# Sheet1.net
KiCad netlist of a schematic drawn in Altium Designer
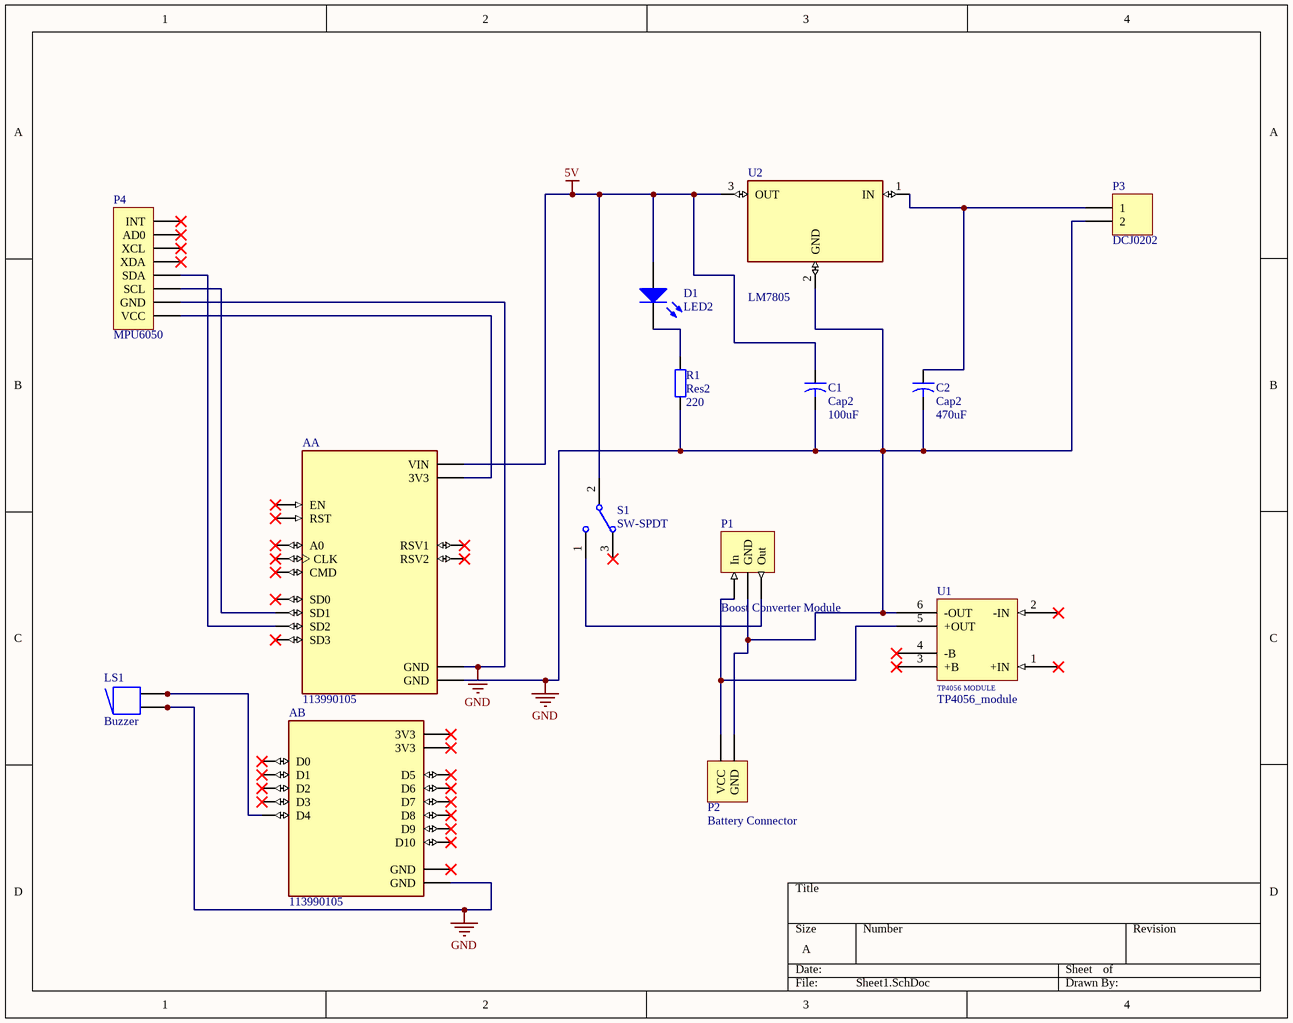
[diagram p0: Sheet1.SchDoc]

(export (version "E")
  (design (tool "Eeschema 10.0.6"))
  (components
    (comp (ref "A")
      (value "113990105")
      (footprint "SEEED_113990105")
      (fields (field (name "MP") "NodeMCU v2") (field (name "MF") "Seeed Technology"))
      (libsource (lib "NodeMCU") (part "113990105"))
    )
    (comp (ref "C1")
      (value "Cap2")
      (footprint "CAPR5-4X5")
      (description "Capacitor")
      (fields (field (name "ALTIUM_VALUE") "100uF") (field (name "PUBLISHER") "Altium Limited"))
      (libsource (lib "Miscellaneous Devices") (part "Cap2"))
    )
    (comp (ref "C2")
      (value "Cap2")
      (footprint "CAPR5-4X5")
      (description "Capacitor")
      (fields (field (name "ALTIUM_VALUE") "470uF") (field (name "PUBLISHER") "Altium Limited"))
      (libsource (lib "Miscellaneous Devices") (part "Cap2"))
    )
    (comp (ref "D1")
      (value "LED2")
      (footprint "3.2X1.6X1.1")
      (description "Typical RED, GREEN, YELLOW, AMBER GaAs LED")
      (fields (field (name "PUBLISHER") "Altium Limited"))
      (libsource (lib "Miscellaneous Devices") (part "LED2"))
    )
    (comp (ref "LS1")
      (value "Buzzer")
      (footprint "ABSM-1574")
      (description "Magnetic Transducer Buzzer")
      (fields (field (name "PUBLISHER") "Altium Limited"))
      (libsource (lib "Miscellaneous Devices") (part "Buzzer"))
    )
    (comp (ref "P1")
      (value "Boost Converter Module")
      (footprint "HDR1X3")
      (description "Header, 3-Pin")
      (fields (field (name "PUBLISHER") "Altium Limited"))
      (libsource (lib "Miscellaneous Connectors") (part "Header 3"))
    )
    (comp (ref "P2")
      (value "Battery Connector")
      (footprint "HDR1X2")
      (description "Header, 2-Pin")
      (fields (field (name "PUBLISHER") "Altium Limited"))
      (libsource (lib "") (part "Header 2_1"))
    )
    (comp (ref "P3")
      (value "DCJ0202")
      (footprint "HDR1X2")
      (description "Header, 2-Pin")
      (fields (field (name "PUBLISHER") "Altium Limited"))
      (libsource (lib "Miscellaneous Connectors") (part "Header 2"))
    )
    (comp (ref "P4")
      (value "MPU6050")
      (footprint "HDR1X8")
      (description "Header, 8-Pin")
      (fields (field (name "PUBLISHER") "Altium Limited"))
      (libsource (lib "Miscellaneous Connectors") (part "Header 8"))
    )
    (comp (ref "R1")
      (value "Res2")
      (footprint "AXIAL-0.4")
      (description "Resistor")
      (fields (field (name "ALTIUM_VALUE") "220") (field (name "PUBLISHER") "Altium Limited"))
      (libsource (lib "Miscellaneous Devices") (part "Res2"))
    )
    (comp (ref "S1")
      (value "SW-SPDT")
      (footprint "TL36WW15050")
      (description "SPDT Subminiature Toggle Switch, Right Angle Mounting, Vertical Actuation")
      (fields (field (name "PUBLISHER") "Altium Limited"))
      (libsource (lib "Miscellaneous Devices") (part "SW-SPDT"))
    )
    (comp (ref "U1")
      (value "TP4056_module")
      (footprint "PCBComponent_1")
      (libsource (lib "TP4056_MODULE") (part "TP4056_module"))
    )
    (comp (ref "U2")
      (value "LM7805")
      (footprint "TO220")
      (description "Linear Voltage Regulator IC 1 Output 1.5A SOT-223-4")
      (fields (field (name "MF") "Texas Instruments"))
      (libsource (lib "LM7805") (part "LM7805"))
    )
  )
  (nets
    (net (code "1") (name "5V") (class "Default")
      (node (ref "A") (pin "J1_15") (pinfunction "VIN_J1_15") (pintype "power_in"))
      (node (ref "C1") (pin "1") (pinfunction "1_1") (pintype "passive"))
      (node (ref "D1") (pin "1") (pinfunction "A_1") (pintype "passive"))
      (node (ref "S1") (pin "2") (pinfunction "2_2") (pintype "passive"))
      (node (ref "U2") (pin "3") (pinfunction "OUT_3") (pintype "bidirectional"))
    )
    (net (code "2") (name "GND") (class "Default")
      (node (ref "A") (pin "J1_10") (pinfunction "GND_J1_10") (pintype "power_in"))
      (node (ref "A") (pin "J1_14") (pinfunction "GND_J1_14") (pintype "power_in"))
      (node (ref "A") (pin "J2_14") (pinfunction "GND_J2_14") (pintype "power_in"))
      (node (ref "C1") (pin "2") (pinfunction "2_2") (pintype "passive"))
      (node (ref "C2") (pin "2") (pinfunction "2_2") (pintype "passive"))
      (node (ref "LS1") (pin "1") (pinfunction "1_1") (pintype "passive"))
      (node (ref "LS1") (pin "1A") (pinfunction "1A_1A") (pintype "passive"))
      (node (ref "P1") (pin "2") (pinfunction "GND_2") (pintype "power_in"))
      (node (ref "P2") (pin "2") (pinfunction "GND_2") (pintype "power_in"))
      (node (ref "P3") (pin "2") (pinfunction "2_2") (pintype "power_in"))
      (node (ref "P4") (pin "2") (pinfunction "GND_2") (pintype "passive"))
      (node (ref "R1") (pin "1") (pinfunction "1_1") (pintype "passive"))
      (node (ref "U1") (pin "6") (pinfunction "-OUT_6") (pintype "power_in"))
      (node (ref "U2") (pin "2") (pinfunction "GND_2") (pintype "bidirectional"))
    )
    (net (code "3") (name "Net-(AA-3V3)") (class "Default")
      (node (ref "A") (pin "J1_11") (pinfunction "3V3_J1_11") (pintype "power_in"))
      (node (ref "P4") (pin "1") (pinfunction "VCC_1") (pintype "passive"))
    )
    (net (code "4") (name "Net-(AA-SD1)") (class "Default")
      (node (ref "A") (pin "J1_6") (pinfunction "SD1_J1_6") (pintype "bidirectional"))
      (node (ref "P4") (pin "3") (pinfunction "SCL_3") (pintype "passive"))
    )
    (net (code "5") (name "Net-(AA-SD2)") (class "Default")
      (node (ref "A") (pin "J1_5") (pinfunction "SD2_J1_5") (pintype "bidirectional"))
      (node (ref "P4") (pin "4") (pinfunction "SDA_4") (pintype "passive"))
    )
    (net (code "6") (name "Net-(AB-D4)") (class "Default")
      (node (ref "A") (pin "J2_5") (pinfunction "D4_J2_5") (pintype "bidirectional"))
      (node (ref "LS1") (pin "2") (pinfunction "2_2") (pintype "passive"))
      (node (ref "LS1") (pin "2A") (pinfunction "2A_2A") (pintype "passive"))
    )
    (net (code "7") (name "Net-(D1-K)") (class "Default")
      (node (ref "D1") (pin "2") (pinfunction "K_2") (pintype "passive"))
      (node (ref "R1") (pin "2") (pinfunction "2_2") (pintype "passive"))
    )
    (net (code "8") (name "Net-(P1-In)") (class "Default")
      (node (ref "P1") (pin "1") (pinfunction "In_1") (pintype "input"))
      (node (ref "P2") (pin "1") (pinfunction "VCC_1") (pintype "power_in"))
      (node (ref "U1") (pin "5") (pinfunction "+OUT_5") (pintype "power_in"))
    )
    (net (code "9") (name "Net-(P1-Out)") (class "Default")
      (node (ref "P1") (pin "3") (pinfunction "Out_3") (pintype "output"))
      (node (ref "S1") (pin "1") (pinfunction "1_1") (pintype "passive"))
    )
    (net (code "10") (name "Net-(U2-IN)") (class "Default")
      (node (ref "C2") (pin "1") (pinfunction "1_1") (pintype "passive"))
      (node (ref "P3") (pin "1") (pinfunction "1_1") (pintype "power_in"))
      (node (ref "U2") (pin "1") (pinfunction "IN_1") (pintype "bidirectional"))
    )
    (net (code "11") (name "unconnected-(AA-A0-PadJ1_1)") (class "Default")
      (node (ref "A") (pin "J1_1") (pinfunction "A0_J1_1") (pintype "bidirectional+no_connect"))
    )
    (net (code "12") (name "unconnected-(AA-CLK-PadJ1_9)") (class "Default")
      (node (ref "A") (pin "J1_9") (pinfunction "CLK_J1_9") (pintype "bidirectional+no_connect"))
    )
    (net (code "13") (name "unconnected-(AA-CMD-PadJ1_7)") (class "Default")
      (node (ref "A") (pin "J1_7") (pinfunction "CMD_J1_7") (pintype "bidirectional+no_connect"))
    )
    (net (code "14") (name "unconnected-(AA-EN-PadJ1_12)") (class "Default")
      (node (ref "A") (pin "J1_12") (pinfunction "EN_J1_12") (pintype "input+no_connect"))
    )
    (net (code "15") (name "unconnected-(AA-RST-PadJ1_13)") (class "Default")
      (node (ref "A") (pin "J1_13") (pinfunction "RST_J1_13") (pintype "input+no_connect"))
    )
    (net (code "16") (name "unconnected-(AA-RSV1-PadJ1_2)") (class "Default")
      (node (ref "A") (pin "J1_2") (pinfunction "RSV1_J1_2") (pintype "bidirectional+no_connect"))
    )
    (net (code "17") (name "unconnected-(AA-RSV2-PadJ1_3)") (class "Default")
      (node (ref "A") (pin "J1_3") (pinfunction "RSV2_J1_3") (pintype "bidirectional+no_connect"))
    )
    (net (code "18") (name "unconnected-(AA-SD0-PadJ1_8)") (class "Default")
      (node (ref "A") (pin "J1_8") (pinfunction "SD0_J1_8") (pintype "bidirectional+no_connect"))
    )
    (net (code "19") (name "unconnected-(AA-SD3-PadJ1_4)") (class "Default")
      (node (ref "A") (pin "J1_4") (pinfunction "SD3_J1_4") (pintype "bidirectional+no_connect"))
    )
    (net (code "20") (name "unconnected-(AB-3V3-PadJ2_6)") (class "Default")
      (node (ref "A") (pin "J2_6") (pinfunction "3V3_J2_6") (pintype "power_in+no_connect"))
    )
    (net (code "21") (name "unconnected-(AB-3V3-PadJ2_15)") (class "Default")
      (node (ref "A") (pin "J2_15") (pinfunction "3V3_J2_15") (pintype "power_in+no_connect"))
    )
    (net (code "22") (name "unconnected-(AB-D0-PadJ2_1)") (class "Default")
      (node (ref "A") (pin "J2_1") (pinfunction "D0_J2_1") (pintype "bidirectional+no_connect"))
    )
    (net (code "23") (name "unconnected-(AB-D1-PadJ2_2)") (class "Default")
      (node (ref "A") (pin "J2_2") (pinfunction "D1_J2_2") (pintype "bidirectional+no_connect"))
    )
    (net (code "24") (name "unconnected-(AB-D2-PadJ2_3)") (class "Default")
      (node (ref "A") (pin "J2_3") (pinfunction "D2_J2_3") (pintype "bidirectional+no_connect"))
    )
    (net (code "25") (name "unconnected-(AB-D3-PadJ2_4)") (class "Default")
      (node (ref "A") (pin "J2_4") (pinfunction "D3_J2_4") (pintype "bidirectional+no_connect"))
    )
    (net (code "26") (name "unconnected-(AB-D5-PadJ2_8)") (class "Default")
      (node (ref "A") (pin "J2_8") (pinfunction "D5_J2_8") (pintype "bidirectional+no_connect"))
    )
    (net (code "27") (name "unconnected-(AB-D6-PadJ2_9)") (class "Default")
      (node (ref "A") (pin "J2_9") (pinfunction "D6_J2_9") (pintype "bidirectional+no_connect"))
    )
    (net (code "28") (name "unconnected-(AB-D7-PadJ2_10)") (class "Default")
      (node (ref "A") (pin "J2_10") (pinfunction "D7_J2_10") (pintype "bidirectional+no_connect"))
    )
    (net (code "29") (name "unconnected-(AB-D8-PadJ2_11)") (class "Default")
      (node (ref "A") (pin "J2_11") (pinfunction "D8_J2_11") (pintype "bidirectional+no_connect"))
    )
    (net (code "30") (name "unconnected-(AB-D9-PadJ2_12)") (class "Default")
      (node (ref "A") (pin "J2_12") (pinfunction "D9_J2_12") (pintype "bidirectional+no_connect"))
    )
    (net (code "31") (name "unconnected-(AB-D10-PadJ2_13)") (class "Default")
      (node (ref "A") (pin "J2_13") (pinfunction "D10_J2_13") (pintype "bidirectional+no_connect"))
    )
    (net (code "32") (name "unconnected-(AB-GND-PadJ2_7)") (class "Default")
      (node (ref "A") (pin "J2_7") (pinfunction "GND_J2_7") (pintype "power_in+no_connect"))
    )
    (net (code "33") (name "unconnected-(P4-AD0-Pad7)") (class "Default")
      (node (ref "P4") (pin "7") (pinfunction "AD0_7") (pintype "passive+no_connect"))
    )
    (net (code "34") (name "unconnected-(P4-INT-Pad8)") (class "Default")
      (node (ref "P4") (pin "8") (pinfunction "INT_8") (pintype "passive+no_connect"))
    )
    (net (code "35") (name "unconnected-(P4-XCL-Pad6)") (class "Default")
      (node (ref "P4") (pin "6") (pinfunction "XCL_6") (pintype "passive+no_connect"))
    )
    (net (code "36") (name "unconnected-(P4-XDA-Pad5)") (class "Default")
      (node (ref "P4") (pin "5") (pinfunction "XDA_5") (pintype "passive+no_connect"))
    )
    (net (code "37") (name "unconnected-(S1-Pad3)") (class "Default")
      (node (ref "S1") (pin "3") (pinfunction "3_3") (pintype "passive+no_connect"))
    )
    (net (code "38") (name "unconnected-(U1-+B-Pad3)") (class "Default")
      (node (ref "U1") (pin "3") (pinfunction "+B_3") (pintype "passive+no_connect"))
    )
    (net (code "39") (name "unconnected-(U1-+IN-Pad1)") (class "Default")
      (node (ref "U1") (pin "1") (pinfunction "+IN_1") (pintype "input+no_connect"))
    )
    (net (code "40") (name "unconnected-(U1--B-Pad4)") (class "Default")
      (node (ref "U1") (pin "4") (pinfunction "-B_4") (pintype "passive+no_connect"))
    )
    (net (code "41") (name "unconnected-(U1--IN-Pad2)") (class "Default")
      (node (ref "U1") (pin "2") (pinfunction "-IN_2") (pintype "input+no_connect"))
    )
  )
)
